# hart_module.net
KiCad netlist of a schematic drawn in EAGLE
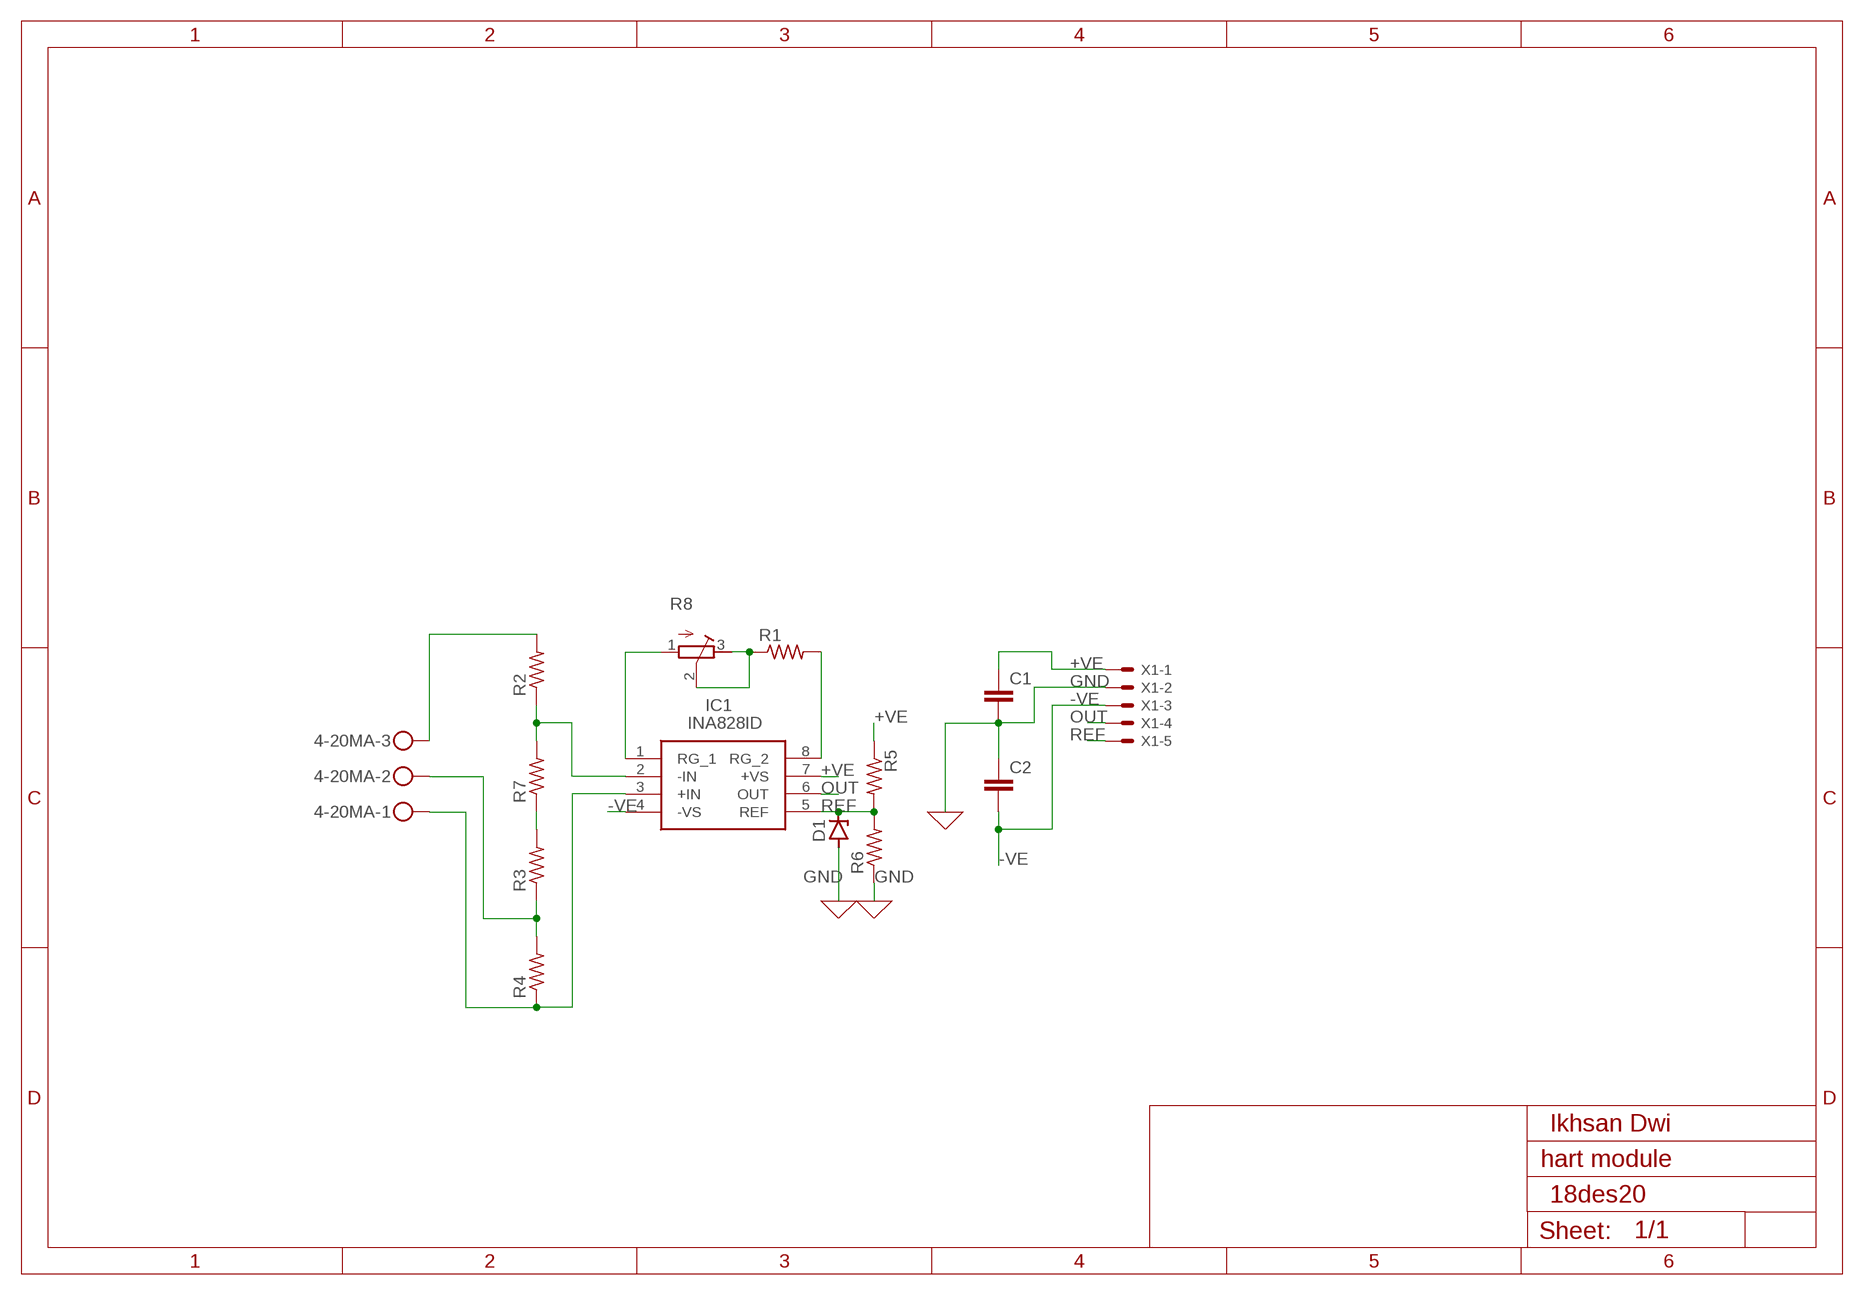
[diagram p0: schematic, sheet 1]

(export (version "E")
  (design (tool "Eeschema 10.0.6"))
  (components
    (comp (ref "4-20MA")
      (value "MKDSN1,5/3-5,08")
      (footprint "eagle-import:MKDSN1,5_3-5,08")
      (libsource (lib "eagle-import") (part "MKDSN1,5/3-5,08"))
    )
    (comp (ref "C1")
      (value "C-EU025-025X050")
      (footprint "eagle-import:C025-025X050")
      (libsource (lib "eagle-import") (part "C-EU025-025X050"))
    )
    (comp (ref "C2")
      (value "C-EU025-025X050")
      (footprint "eagle-import:C025-025X050")
      (libsource (lib "eagle-import") (part "C-EU025-025X050"))
    )
    (comp (ref "D1")
      (value "ZENER-DIODEDO35Z10")
      (footprint "eagle-import:DO35Z10")
      (libsource (lib "eagle-import") (part "ZENER-DIODEDO35Z10"))
    )
    (comp (ref "IC1")
      (value "INA828ID")
      (footprint "eagle-import:SOIC127P600X175-8N")
      (fields (field (name "MOUSER_PART_NUMBER") "595-INA828ID"))
      (libsource (lib "eagle-import") (part "INA828ID"))
    )
    (comp (ref "R1")
      (value "R-US_R1206W")
      (footprint "eagle-import:R1206W")
      (libsource (lib "eagle-import") (part "R-US_R1206W"))
    )
    (comp (ref "R2")
      (value "R-US_R1206W")
      (footprint "eagle-import:R1206W")
      (libsource (lib "eagle-import") (part "R-US_R1206W"))
    )
    (comp (ref "R3")
      (value "R-US_R1206W")
      (footprint "eagle-import:R1206W")
      (libsource (lib "eagle-import") (part "R-US_R1206W"))
    )
    (comp (ref "R4")
      (value "R-US_R1206W")
      (footprint "eagle-import:R1206W")
      (libsource (lib "eagle-import") (part "R-US_R1206W"))
    )
    (comp (ref "R5")
      (value "R-US_R1206W")
      (footprint "eagle-import:R1206W")
      (libsource (lib "eagle-import") (part "R-US_R1206W"))
    )
    (comp (ref "R6")
      (value "R-US_R1206W")
      (footprint "eagle-import:R1206W")
      (libsource (lib "eagle-import") (part "R-US_R1206W"))
    )
    (comp (ref "R7")
      (value "R-US_R1206W")
      (footprint "eagle-import:R1206W")
      (libsource (lib "eagle-import") (part "R-US_R1206W"))
    )
    (comp (ref "R8")
      (value "R-TRIMM3339P")
      (footprint "eagle-import:RTRIM3339P")
      (libsource (lib "eagle-import") (part "R-TRIMM3339P"))
    )
    (comp (ref "X1")
      (value "22-23-2051")
      (footprint "eagle-import:22-23-2051")
      (fields (field (name "MF") "MOLEX"))
      (libsource (lib "eagle-import") (part "22-23-2051"))
    )
  )
  (nets
    (net (code "1") (name "/+VE") (class "Default")
      (node (ref "C1") (pin "1") (pinfunction "1_1") (pintype "passive"))
      (node (ref "IC1") (pin "7") (pinfunction "+VS_7") (pintype "bidirectional"))
      (node (ref "R5") (pin "1") (pinfunction "1_1") (pintype "passive"))
      (node (ref "X1") (pin "1") (pinfunction "S_1") (pintype "passive"))
    )
    (net (code "2") (name "/-VE") (class "Default")
      (node (ref "C2") (pin "2") (pinfunction "2_2") (pintype "passive"))
      (node (ref "IC1") (pin "4") (pinfunction "-VS_4") (pintype "bidirectional"))
      (node (ref "X1") (pin "3") (pinfunction "S_3") (pintype "passive"))
    )
    (net (code "3") (name "/OUT") (class "Default")
      (node (ref "IC1") (pin "6") (pinfunction "OUT_6") (pintype "bidirectional"))
      (node (ref "X1") (pin "4") (pinfunction "S_4") (pintype "passive"))
    )
    (net (code "4") (name "/REF") (class "Default")
      (node (ref "D1") (pin "C") (pinfunction "C_C") (pintype "passive"))
      (node (ref "IC1") (pin "5") (pinfunction "REF_5") (pintype "bidirectional"))
      (node (ref "R5") (pin "2") (pinfunction "2_2") (pintype "passive"))
      (node (ref "R6") (pin "2") (pinfunction "2_2") (pintype "passive"))
      (node (ref "X1") (pin "5") (pinfunction "S_5") (pintype "passive"))
    )
    (net (code "5") (name "GND") (class "Default")
      (node (ref "C1") (pin "2") (pinfunction "2_2") (pintype "passive"))
      (node (ref "C2") (pin "1") (pinfunction "1_1") (pintype "passive"))
      (node (ref "D1") (pin "A") (pinfunction "A_A") (pintype "passive"))
      (node (ref "R6") (pin "1") (pinfunction "1_1") (pintype "passive"))
      (node (ref "X1") (pin "2") (pinfunction "S_2") (pintype "passive"))
    )
    (net (code "6") (name "Net-(4-20MAA-KL)") (class "Default")
      (node (ref "4-20MA") (pin "1") (pinfunction "KL_1") (pintype "passive"))
      (node (ref "IC1") (pin "3") (pinfunction "+IN_3") (pintype "bidirectional"))
      (node (ref "R4") (pin "1") (pinfunction "1_1") (pintype "passive"))
    )
    (net (code "7") (name "Net-(4-20MAB-KL)") (class "Default")
      (node (ref "4-20MA") (pin "2") (pinfunction "KL_2") (pintype "passive"))
      (node (ref "R3") (pin "1") (pinfunction "1_1") (pintype "passive"))
      (node (ref "R4") (pin "2") (pinfunction "2_2") (pintype "passive"))
    )
    (net (code "8") (name "Net-(4-20MAC-KL)") (class "Default")
      (node (ref "4-20MA") (pin "3") (pinfunction "KL_3") (pintype "passive"))
      (node (ref "R2") (pin "2") (pinfunction "2_2") (pintype "passive"))
    )
    (net (code "9") (name "Net-(IC1--IN)") (class "Default")
      (node (ref "IC1") (pin "2") (pinfunction "-IN_2") (pintype "bidirectional"))
      (node (ref "R2") (pin "1") (pinfunction "1_1") (pintype "passive"))
      (node (ref "R7") (pin "2") (pinfunction "2_2") (pintype "passive"))
    )
    (net (code "10") (name "Net-(IC1-RG_1)") (class "Default")
      (node (ref "IC1") (pin "1") (pinfunction "RG_1_1") (pintype "bidirectional"))
      (node (ref "R8") (pin "1") (pinfunction "A_1") (pintype "passive"))
    )
    (net (code "11") (name "Net-(IC1-RG_2)") (class "Default")
      (node (ref "IC1") (pin "8") (pinfunction "RG_2_8") (pintype "bidirectional"))
      (node (ref "R1") (pin "2") (pinfunction "2_2") (pintype "passive"))
    )
    (net (code "12") (name "Net-(R3-Pad2)") (class "Default")
      (node (ref "R3") (pin "2") (pinfunction "2_2") (pintype "passive"))
      (node (ref "R7") (pin "1") (pinfunction "1_1") (pintype "passive"))
    )
    (net (code "13") (name "Net-(R8-E)") (class "Default")
      (node (ref "R1") (pin "1") (pinfunction "1_1") (pintype "passive"))
      (node (ref "R8") (pin "2") (pinfunction "S_2") (pintype "passive"))
      (node (ref "R8") (pin "3") (pinfunction "E_3") (pintype "passive"))
    )
  )
)
